# 4_x_MIDI_Thru_Box_with_LED.net
KiCad netlist of a schematic drawn in EAGLE
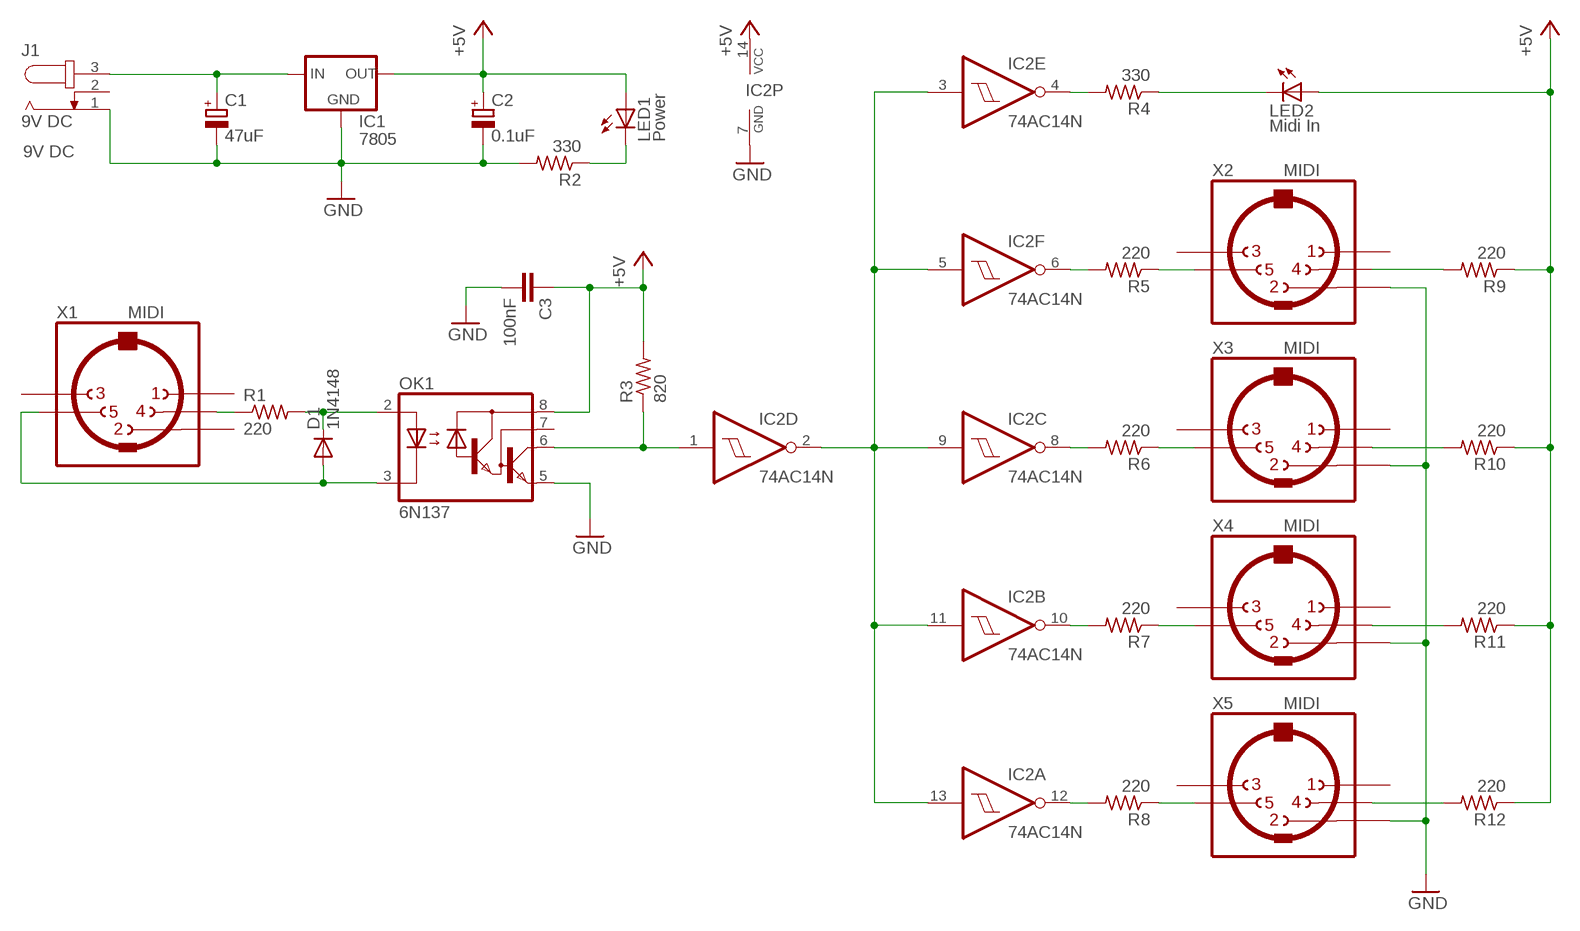
[diagram p0: schematic, sheet 1]

(export (version "E")
  (design (tool "Eeschema 10.0.6"))
  (components
    (comp (ref "C1")
      (value "47uF")
      (footprint "eagle-import:TT2D6")
      (libsource (lib "eagle-import") (part "CPOL-EUTT2D6"))
    )
    (comp (ref "C2")
      (value "0.1uF")
      (footprint "eagle-import:TT2D6")
      (libsource (lib "eagle-import") (part "CPOL-EUTT2D6"))
    )
    (comp (ref "C3")
      (value "100nF")
      (footprint "eagle-import:C025-024X044")
      (libsource (lib "eagle-import") (part "C-EU025-024X044"))
    )
    (comp (ref "D1")
      (value "1N4148")
      (footprint "eagle-import:D-5")
      (libsource (lib "eagle-import") (part "DIODE-D-5"))
    )
    (comp (ref "IC1")
      (value "7805")
      (footprint "eagle-import:78XXS")
      (libsource (lib "eagle-import") (part "78XXS"))
    )
    (comp (ref "IC2")
      (value "74AC14N")
      (footprint "eagle-import:DIL14")
      (libsource (lib "eagle-import") (part "7414NAC"))
    )
    (comp (ref "J1")
      (value "9V DC")
      (footprint "eagle-import:SPC4078_BIG_HOLES")
      (libsource (lib "eagle-import") (part "JACK-PLUG2"))
    )
    (comp (ref "LED1")
      (value "Power")
      (footprint "eagle-import:LED3MM")
      (libsource (lib "eagle-import") (part "LED3MM"))
    )
    (comp (ref "LED2")
      (value "Midi In")
      (footprint "eagle-import:LED3MM")
      (libsource (lib "eagle-import") (part "LED3MM"))
    )
    (comp (ref "OK1")
      (value "6N137")
      (footprint "eagle-import:DIL08")
      (libsource (lib "eagle-import") (part "6N138"))
    )
    (comp (ref "R1")
      (value "220")
      (footprint "eagle-import:0204_7")
      (libsource (lib "eagle-import") (part "R-US_0204/7"))
    )
    (comp (ref "R2")
      (value "330")
      (footprint "eagle-import:0204_7")
      (libsource (lib "eagle-import") (part "R-US_0204/7"))
    )
    (comp (ref "R3")
      (value "820")
      (footprint "eagle-import:0204_7")
      (libsource (lib "eagle-import") (part "R-US_0204/7"))
    )
    (comp (ref "R4")
      (value "330")
      (footprint "eagle-import:0204_7")
      (libsource (lib "eagle-import") (part "R-US_0204/7"))
    )
    (comp (ref "R5")
      (value "220")
      (footprint "eagle-import:0204_7")
      (libsource (lib "eagle-import") (part "R-US_0204/7"))
    )
    (comp (ref "R6")
      (value "220")
      (footprint "eagle-import:0204_7")
      (libsource (lib "eagle-import") (part "R-US_0204/7"))
    )
    (comp (ref "R7")
      (value "220")
      (footprint "eagle-import:0204_7")
      (libsource (lib "eagle-import") (part "R-US_0204/7"))
    )
    (comp (ref "R8")
      (value "220")
      (footprint "eagle-import:0204_7")
      (libsource (lib "eagle-import") (part "R-US_0204/7"))
    )
    (comp (ref "R9")
      (value "220")
      (footprint "eagle-import:0204_7")
      (libsource (lib "eagle-import") (part "R-US_0204/7"))
    )
    (comp (ref "R10")
      (value "220")
      (footprint "eagle-import:0204_7")
      (libsource (lib "eagle-import") (part "R-US_0204/7"))
    )
    (comp (ref "R11")
      (value "220")
      (footprint "eagle-import:0204_7")
      (libsource (lib "eagle-import") (part "R-US_0204/7"))
    )
    (comp (ref "R12")
      (value "220")
      (footprint "eagle-import:0204_7")
      (libsource (lib "eagle-import") (part "R-US_0204/7"))
    )
    (comp (ref "X1")
      (value "MIDI")
      (footprint "eagle-import:MAB5SH")
      (libsource (lib "eagle-import") (part "MAB5SH"))
    )
    (comp (ref "X2")
      (value "MIDI")
      (footprint "eagle-import:MAB5SH")
      (libsource (lib "eagle-import") (part "MAB5SH"))
    )
    (comp (ref "X3")
      (value "MIDI")
      (footprint "eagle-import:MAB5SH")
      (libsource (lib "eagle-import") (part "MAB5SH"))
    )
    (comp (ref "X4")
      (value "MIDI")
      (footprint "eagle-import:MAB5SH")
      (libsource (lib "eagle-import") (part "MAB5SH"))
    )
    (comp (ref "X5")
      (value "MIDI")
      (footprint "eagle-import:MAB5SH")
      (libsource (lib "eagle-import") (part "MAB5SH"))
    )
  )
  (nets
    (net (code "1") (name "+5V") (class "Default")
      (node (ref "C2") (pin "+") (pinfunction "+_+") (pintype "passive"))
      (node (ref "C3") (pin "1") (pinfunction "1_1") (pintype "passive"))
      (node (ref "IC1") (pin "OUT") (pinfunction "OUT_OUT") (pintype "passive"))
      (node (ref "IC2") (pin "14") (pinfunction "VCC_14") (pintype "power_in"))
      (node (ref "LED1") (pin "A") (pinfunction "A_A") (pintype "passive"))
      (node (ref "LED2") (pin "A") (pinfunction "A_A") (pintype "passive"))
      (node (ref "OK1") (pin "8") (pinfunction "VCC_8") (pintype "passive"))
      (node (ref "R10") (pin "1") (pinfunction "1_1") (pintype "passive"))
      (node (ref "R11") (pin "1") (pinfunction "1_1") (pintype "passive"))
      (node (ref "R12") (pin "1") (pinfunction "1_1") (pintype "passive"))
      (node (ref "R3") (pin "2") (pinfunction "2_2") (pintype "passive"))
      (node (ref "R9") (pin "1") (pinfunction "1_1") (pintype "passive"))
    )
    (net (code "2") (name "GND") (class "Default")
      (node (ref "C1") (pin "-") (pinfunction "-_-") (pintype "passive"))
      (node (ref "C2") (pin "-") (pinfunction "-_-") (pintype "passive"))
      (node (ref "C3") (pin "2") (pinfunction "2_2") (pintype "passive"))
      (node (ref "IC1") (pin "GND") (pinfunction "GND_GND") (pintype "input"))
      (node (ref "IC2") (pin "7") (pinfunction "GND_7") (pintype "power_in"))
      (node (ref "J1") (pin "1") (pinfunction "1_1") (pintype "passive"))
      (node (ref "OK1") (pin "5") (pinfunction "GND_5") (pintype "passive"))
      (node (ref "R2") (pin "2") (pinfunction "2_2") (pintype "passive"))
      (node (ref "X2") (pin "2") (pinfunction "2_2") (pintype "passive"))
      (node (ref "X3") (pin "2") (pinfunction "2_2") (pintype "passive"))
      (node (ref "X4") (pin "2") (pinfunction "2_2") (pintype "passive"))
      (node (ref "X5") (pin "2") (pinfunction "2_2") (pintype "passive"))
    )
    (net (code "3") (name "Net-(C1-Pad+)") (class "Default")
      (node (ref "C1") (pin "+") (pinfunction "+_+") (pintype "passive"))
      (node (ref "IC1") (pin "IN") (pinfunction "IN_IN") (pintype "input"))
      (node (ref "J1") (pin "3") (pinfunction "3_3") (pintype "passive"))
    )
    (net (code "4") (name "Net-(IC2A-I)") (class "Default")
      (node (ref "IC2") (pin "11") (pinfunction "I_11") (pintype "input"))
      (node (ref "IC2") (pin "13") (pinfunction "I_13") (pintype "input"))
      (node (ref "IC2") (pin "2") (pinfunction "O_2") (pintype "output"))
      (node (ref "IC2") (pin "3") (pinfunction "I_3") (pintype "input"))
      (node (ref "IC2") (pin "5") (pinfunction "I_5") (pintype "input"))
      (node (ref "IC2") (pin "9") (pinfunction "I_9") (pintype "input"))
    )
    (net (code "5") (name "Net-(IC2A-O)") (class "Default")
      (node (ref "IC2") (pin "12") (pinfunction "O_12") (pintype "output"))
      (node (ref "R8") (pin "2") (pinfunction "2_2") (pintype "passive"))
    )
    (net (code "6") (name "Net-(IC2B-O)") (class "Default")
      (node (ref "IC2") (pin "10") (pinfunction "O_10") (pintype "output"))
      (node (ref "R7") (pin "2") (pinfunction "2_2") (pintype "passive"))
    )
    (net (code "7") (name "Net-(IC2C-O)") (class "Default")
      (node (ref "IC2") (pin "8") (pinfunction "O_8") (pintype "output"))
      (node (ref "R6") (pin "2") (pinfunction "2_2") (pintype "passive"))
    )
    (net (code "8") (name "Net-(IC2D-I)") (class "Default")
      (node (ref "IC2") (pin "1") (pinfunction "I_1") (pintype "input"))
      (node (ref "OK1") (pin "6") (pinfunction "VO_6") (pintype "passive"))
      (node (ref "R3") (pin "1") (pinfunction "1_1") (pintype "passive"))
    )
    (net (code "9") (name "Net-(IC2E-O)") (class "Default")
      (node (ref "IC2") (pin "4") (pinfunction "O_4") (pintype "output"))
      (node (ref "R4") (pin "2") (pinfunction "2_2") (pintype "passive"))
    )
    (net (code "10") (name "Net-(IC2F-O)") (class "Default")
      (node (ref "IC2") (pin "6") (pinfunction "O_6") (pintype "output"))
      (node (ref "R5") (pin "2") (pinfunction "2_2") (pintype "passive"))
    )
    (net (code "11") (name "Net-(LED1-C)") (class "Default")
      (node (ref "LED1") (pin "K") (pinfunction "C_K") (pintype "passive"))
      (node (ref "R2") (pin "1") (pinfunction "1_1") (pintype "passive"))
    )
    (net (code "12") (name "Net-(LED2-C)") (class "Default")
      (node (ref "LED2") (pin "K") (pinfunction "C_K") (pintype "passive"))
      (node (ref "R4") (pin "1") (pinfunction "1_1") (pintype "passive"))
    )
    (net (code "13") (name "Net-(OK1-A)") (class "Default")
      (node (ref "D1") (pin "C") (pinfunction "C_C") (pintype "passive"))
      (node (ref "OK1") (pin "2") (pinfunction "A_2") (pintype "passive"))
      (node (ref "R1") (pin "2") (pinfunction "2_2") (pintype "passive"))
    )
    (net (code "14") (name "Net-(OK1-C)") (class "Default")
      (node (ref "D1") (pin "A") (pinfunction "A_A") (pintype "passive"))
      (node (ref "OK1") (pin "3") (pinfunction "C_3") (pintype "passive"))
      (node (ref "X1") (pin "5") (pinfunction "5_5") (pintype "passive"))
    )
    (net (code "15") (name "Net-(R1-Pad1)") (class "Default")
      (node (ref "R1") (pin "1") (pinfunction "1_1") (pintype "passive"))
      (node (ref "X1") (pin "4") (pinfunction "4_4") (pintype "passive"))
    )
    (net (code "16") (name "Net-(R5-Pad1)") (class "Default")
      (node (ref "R5") (pin "1") (pinfunction "1_1") (pintype "passive"))
      (node (ref "X2") (pin "5") (pinfunction "5_5") (pintype "passive"))
    )
    (net (code "17") (name "Net-(R6-Pad1)") (class "Default")
      (node (ref "R6") (pin "1") (pinfunction "1_1") (pintype "passive"))
      (node (ref "X3") (pin "5") (pinfunction "5_5") (pintype "passive"))
    )
    (net (code "18") (name "Net-(R7-Pad1)") (class "Default")
      (node (ref "R7") (pin "1") (pinfunction "1_1") (pintype "passive"))
      (node (ref "X4") (pin "5") (pinfunction "5_5") (pintype "passive"))
    )
    (net (code "19") (name "Net-(R8-Pad1)") (class "Default")
      (node (ref "R8") (pin "1") (pinfunction "1_1") (pintype "passive"))
      (node (ref "X5") (pin "5") (pinfunction "5_5") (pintype "passive"))
    )
    (net (code "20") (name "Net-(R9-Pad2)") (class "Default")
      (node (ref "R9") (pin "2") (pinfunction "2_2") (pintype "passive"))
      (node (ref "X2") (pin "4") (pinfunction "4_4") (pintype "passive"))
    )
    (net (code "21") (name "Net-(R10-Pad2)") (class "Default")
      (node (ref "R10") (pin "2") (pinfunction "2_2") (pintype "passive"))
      (node (ref "X3") (pin "4") (pinfunction "4_4") (pintype "passive"))
    )
    (net (code "22") (name "Net-(R11-Pad2)") (class "Default")
      (node (ref "R11") (pin "2") (pinfunction "2_2") (pintype "passive"))
      (node (ref "X4") (pin "4") (pinfunction "4_4") (pintype "passive"))
    )
    (net (code "23") (name "Net-(R12-Pad2)") (class "Default")
      (node (ref "R12") (pin "2") (pinfunction "2_2") (pintype "passive"))
      (node (ref "X5") (pin "4") (pinfunction "4_4") (pintype "passive"))
    )
    (net (code "24") (name "unconnected-(J1-Pad2)") (class "Default")
      (node (ref "J1") (pin "2") (pinfunction "2_2") (pintype "passive"))
    )
    (net (code "25") (name "unconnected-(OK1-VB-Pad7)") (class "Default")
      (node (ref "OK1") (pin "7") (pinfunction "VB_7") (pintype "passive"))
    )
    (net (code "26") (name "unconnected-(X1-Pad1)") (class "Default")
      (node (ref "X1") (pin "1") (pinfunction "1_1") (pintype "passive"))
    )
    (net (code "27") (name "unconnected-(X1-Pad2)") (class "Default")
      (node (ref "X1") (pin "2") (pinfunction "2_2") (pintype "passive"))
    )
    (net (code "28") (name "unconnected-(X1-Pad3)") (class "Default")
      (node (ref "X1") (pin "3") (pinfunction "3_3") (pintype "passive"))
    )
    (net (code "29") (name "unconnected-(X2-Pad1)") (class "Default")
      (node (ref "X2") (pin "1") (pinfunction "1_1") (pintype "passive"))
    )
    (net (code "30") (name "unconnected-(X2-Pad3)") (class "Default")
      (node (ref "X2") (pin "3") (pinfunction "3_3") (pintype "passive"))
    )
    (net (code "31") (name "unconnected-(X3-Pad1)") (class "Default")
      (node (ref "X3") (pin "1") (pinfunction "1_1") (pintype "passive"))
    )
    (net (code "32") (name "unconnected-(X3-Pad3)") (class "Default")
      (node (ref "X3") (pin "3") (pinfunction "3_3") (pintype "passive"))
    )
    (net (code "33") (name "unconnected-(X4-Pad1)") (class "Default")
      (node (ref "X4") (pin "1") (pinfunction "1_1") (pintype "passive"))
    )
    (net (code "34") (name "unconnected-(X4-Pad3)") (class "Default")
      (node (ref "X4") (pin "3") (pinfunction "3_3") (pintype "passive"))
    )
    (net (code "35") (name "unconnected-(X5-Pad1)") (class "Default")
      (node (ref "X5") (pin "1") (pinfunction "1_1") (pintype "passive"))
    )
    (net (code "36") (name "unconnected-(X5-Pad3)") (class "Default")
      (node (ref "X5") (pin "3") (pinfunction "3_3") (pintype "passive"))
    )
  )
)
